# STM32F103C8T6.net
KiCad netlist of a schematic drawn in Altium Designer
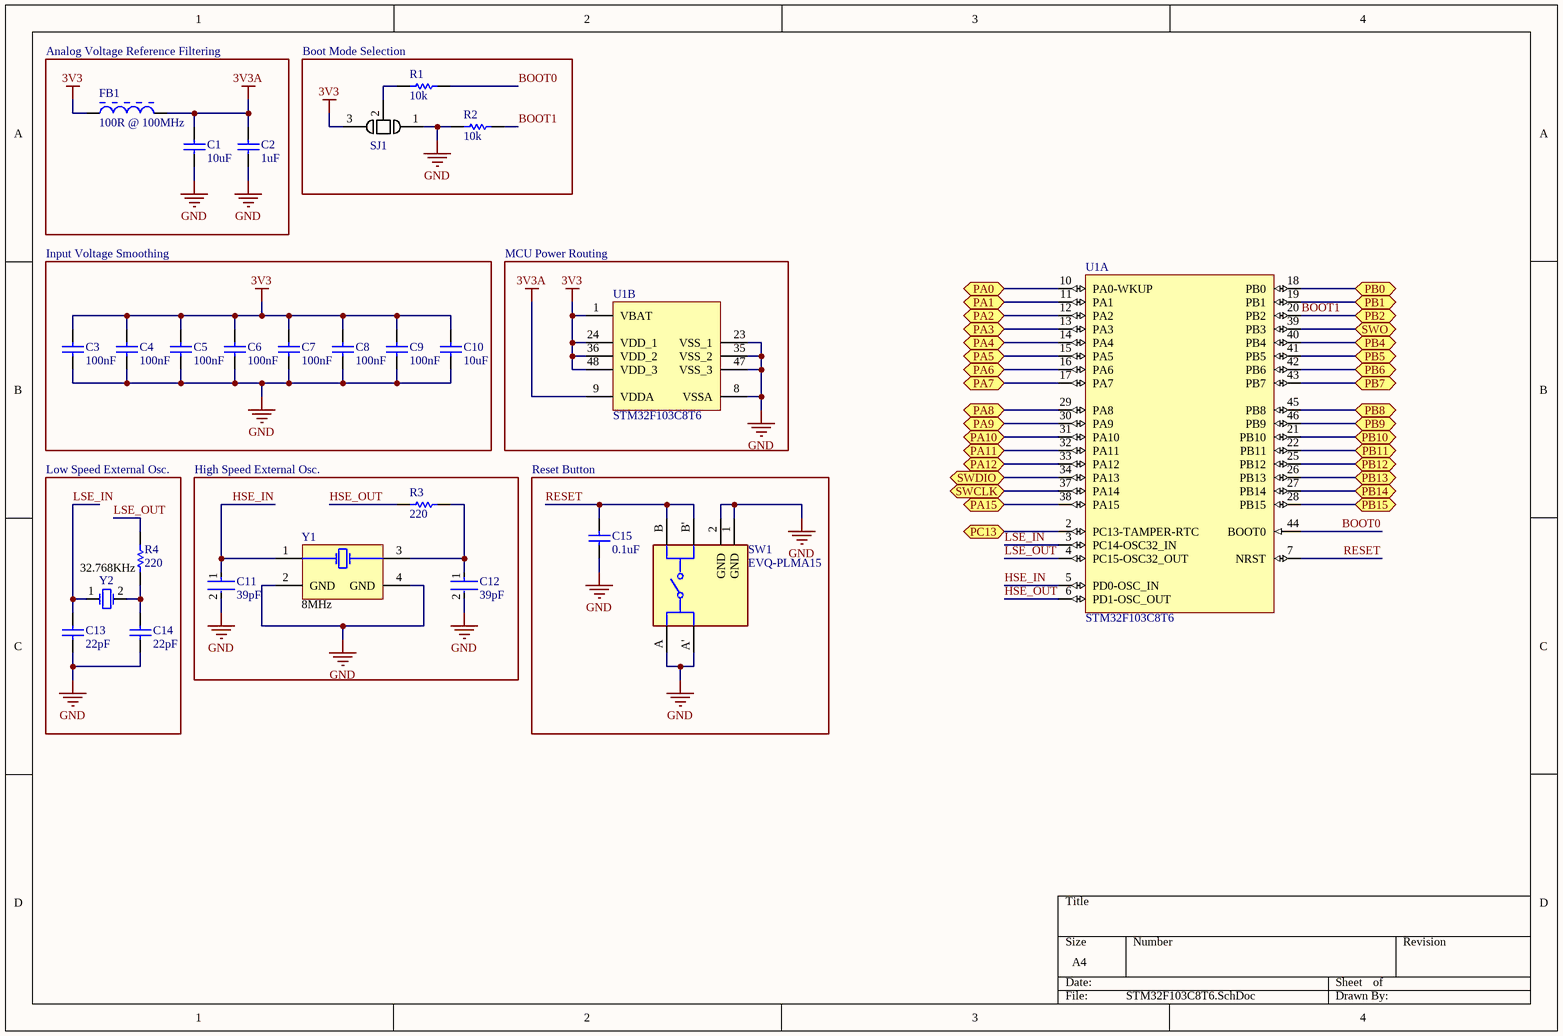
[diagram p0: STM32F103C8T6.SchDoc]

(export (version "E")
  (design (tool "Eeschema 10.0.6"))
  (components
    (comp (ref "C1")
      (value "10uF")
      (footprint "CAPC3216X180X50LL20T30")
      (description "Chip Capacitor, 10 uF, +/- 10%, 25 V, -55 to 85 degC, 1206 (3216 Metric), RoHS, Tape and Reel")
      (fields
        (field (name "MANUFACTURER") "Samsung Electro-Mechanics")
        (field (name "MANUFACTURER PART NUMBER") "CL31A106KAHNNNE")
      )
      (libsource (lib "Altium Content Vault") (part "CAP-NP-2"))
    )
    (comp (ref "C2")
      (value "1uF")
      (footprint "CAPC2013X140X50NL20T25")
      (fields
        (field (name "PART NUMBER") "C0805C105J4RACTU")
        (field (name "MANUFACTURER") "Kemet")
        (field (name "TOLERANCE") "5%")
      )
      (libsource (lib "Altium Content Vault") (part "CAP"))
    )
    (comp (ref "C3")
      (value "100nF")
      (footprint "CAPC2013X94X50LL20T25")
      (description "Chip Capacitor, 0.1 uF, +/- 5%, 50 V, -55 to 125 degC, 0805 (2012 Metric), RoHS, Tape and Reel")
      (fields (field (name "TOLERANCE") "5%") (field (name "MANUFACTURER") "AVX"))
      (libsource (lib "Altium Content Vault") (part "CAP-NP-2"))
    )
    (comp (ref "C4")
      (value "100nF")
      (footprint "CAPC2013X94X50LL20T25")
      (description "Chip Capacitor, 0.1 uF, +/- 5%, 50 V, -55 to 125 degC, 0805 (2012 Metric), RoHS, Tape and Reel")
      (fields (field (name "TOLERANCE") "5%") (field (name "MANUFACTURER") "AVX"))
      (libsource (lib "Altium Content Vault") (part "CAP-NP-2"))
    )
    (comp (ref "C5")
      (value "100nF")
      (footprint "CAPC2013X94X50LL20T25")
      (description "Chip Capacitor, 0.1 uF, +/- 5%, 50 V, -55 to 125 degC, 0805 (2012 Metric), RoHS, Tape and Reel")
      (fields (field (name "TOLERANCE") "5%") (field (name "MANUFACTURER") "AVX"))
      (libsource (lib "Altium Content Vault") (part "CAP-NP-2"))
    )
    (comp (ref "C6")
      (value "100nF")
      (footprint "CAPC2013X94X50LL20T25")
      (description "Chip Capacitor, 0.1 uF, +/- 5%, 50 V, -55 to 125 degC, 0805 (2012 Metric), RoHS, Tape and Reel")
      (fields (field (name "TOLERANCE") "5%") (field (name "MANUFACTURER") "AVX"))
      (libsource (lib "Altium Content Vault") (part "CAP-NP-2"))
    )
    (comp (ref "C7")
      (value "100nF")
      (footprint "CAPC2013X94X50LL20T25")
      (description "Chip Capacitor, 0.1 uF, +/- 5%, 50 V, -55 to 125 degC, 0805 (2012 Metric), RoHS, Tape and Reel")
      (fields (field (name "TOLERANCE") "5%") (field (name "MANUFACTURER") "AVX"))
      (libsource (lib "Altium Content Vault") (part "CAP-NP-2"))
    )
    (comp (ref "C8")
      (value "100nF")
      (footprint "CAPC2013X94X50LL20T25")
      (description "Chip Capacitor, 0.1 uF, +/- 5%, 50 V, -55 to 125 degC, 0805 (2012 Metric), RoHS, Tape and Reel")
      (fields (field (name "TOLERANCE") "5%") (field (name "MANUFACTURER") "AVX"))
      (libsource (lib "Altium Content Vault") (part "CAP-NP-2"))
    )
    (comp (ref "C9")
      (value "100nF")
      (footprint "CAPC2013X94X50LL20T25")
      (description "Chip Capacitor, 0.1 uF, +/- 5%, 50 V, -55 to 125 degC, 0805 (2012 Metric), RoHS, Tape and Reel")
      (fields (field (name "TOLERANCE") "5%") (field (name "MANUFACTURER") "AVX"))
      (libsource (lib "Altium Content Vault") (part "CAP-NP-2"))
    )
    (comp (ref "C10")
      (value "10uF")
      (footprint "CAPC3216X180X50LL20T30")
      (description "Chip Capacitor, 10 uF, +/- 10%, 25 V, -55 to 85 degC, 1206 (3216 Metric), RoHS, Tape and Reel")
      (fields
        (field (name "MANUFACTURER") "Samsung Electro-Mechanics")
        (field (name "MANUFACTURER PART NUMBER") "CL31A106KAHNNNE")
      )
      (libsource (lib "Altium Content Vault") (part "CAP-NP-2"))
    )
    (comp (ref "C11")
      (value "39pF")
      (footprint "FP-CL21-IPC_B")
      (description "CL21 Series 0805 39pF 50V ±5% Tolerance C0G Multilayer Ceramic Chip Capacitor")
      (fields (field (name "TOLERANCE") "5%") (field (name "VOLTAGE") "50V"))
      (libsource (lib "Altium Content Vault") (part "b4654b650e69147ec39a6b967a45e02"))
    )
    (comp (ref "C12")
      (value "39pF")
      (footprint "FP-CL21-IPC_B")
      (description "CL21 Series 0805 39pF 50V ±5% Tolerance C0G Multilayer Ceramic Chip Capacitor")
      (fields (field (name "TOLERANCE") "5%") (field (name "VOLTAGE") "50V"))
      (libsource (lib "Altium Content Vault") (part "b4654b650e69147ec39a6b967a45e02"))
    )
    (comp (ref "C13")
      (value "22pF")
      (footprint "CAPC2012X88X50ML20T25")
      (fields
        (field (name "MANUFACTURER") "Kemet")
        (field (name "PART NUMBER") "C0805C220J5GACTU")
        (field (name "TOLERANCE") "5%")
      )
      (libsource (lib "Altium Content Vault") (part "CAP"))
    )
    (comp (ref "C14")
      (value "22pF")
      (footprint "CAPC2012X88X50ML20T25")
      (fields
        (field (name "MANUFACTURER") "Kemet")
        (field (name "PART NUMBER") "C0805C220J5GACTU")
        (field (name "TOLERANCE") "5%")
      )
      (libsource (lib "Altium Content Vault") (part "CAP"))
    )
    (comp (ref "C15")
      (value "0.1uF")
      (footprint "CAPC2013X95X45ML10T25")
      (description "Chip Capacitor, 0.1 uF, +/- 10%, 50 V, 0805 (2012 Metric), RoHS, Tape and Reel")
      (fields
        (field (name "MANUFACTURER") "Samsung Electro-Mechanics")
        (field (name "MANUFACTURER PART NUMBER") "CL21B104KBCNNNC")
      )
      (libsource (lib "Altium Content Vault") (part "CAP-NP-2"))
    )
    (comp (ref "FB1")
      (value "100R @ 100MHz")
      (footprint "MURA-BLM18PG_KG-B25-CHIP-2_V1")
      (fields
        (field (name "PARTNUMBER") "BLM18PG121SN1D")
        (field (name "MANUFACTURER") "Murata")
        (field (name "TOLERANCE") "25%")
      )
      (libsource (lib "Altium Content Vault") (part "MURA-FB-2"))
    )
    (comp (ref "R1")
      (value "10k")
      (footprint "RESC2013X70X40LL20T20")
      (fields
        (field (name "PART NUMBER") "ERJ-6GEYJ103V")
        (field (name "MANUFACTURER") "Panasonic")
        (field (name "TOLERANCE") "5%")
      )
      (libsource (lib "Altium Content Vault") (part "RES"))
    )
    (comp (ref "R2")
      (value "10k")
      (footprint "RESC2013X70X40LL20T20")
      (fields
        (field (name "PART NUMBER") "ERJ-6GEYJ103V")
        (field (name "MANUFACTURER") "Panasonic")
        (field (name "TOLERANCE") "5%")
      )
      (libsource (lib "Altium Content Vault") (part "RES"))
    )
    (comp (ref "R3")
      (value "220")
      (footprint "RESC2013X70X40NL20T20")
      (fields
        (field (name "PART NUMBER") "ERJ6ENF2200V")
        (field (name "MANUFACTURER") "Panasonic")
        (field (name "MANUFACTURER PART NUMBER") "ERJ-6ENF2200V")
      )
      (libsource (lib "Altium Content Vault") (part "RES"))
    )
    (comp (ref "R4")
      (value "220")
      (footprint "RESC2013X70X40NL20T20")
      (fields
        (field (name "PART NUMBER") "ERJ6ENF2200V")
        (field (name "MANUFACTURER") "Panasonic")
        (field (name "MANUFACTURER PART NUMBER") "ERJ-6ENF2200V")
      )
      (libsource (lib "Altium Content Vault") (part "RES"))
    )
    (comp (ref "SJ1")
      (value "Switchable Jumper")
      (footprint "6mil Switchable")
      (description "Switchable Solder Jumper to choose between two connections.")
      (libsource (lib "Solder Jumpers") (part "Switchable Jumper"))
    )
    (comp (ref "SW1")
      (value "EVQ-PLMA15")
      (footprint "FP-EVQ-PLMA15-MFG")
      (description "SWITCH TACTILE SPST-NO 0.02A 15V")
      (fields
        (field (name "OCTOPART") "https://octopart.com/evq-plma15-panasonic-39850235")
        (field (name "MANUFACTURER") "Panasonic Electronic Components")
      )
      (libsource (lib "Altium Content Vault") (part "fc7b47d2e4813f0909612a6c4f63938"))
    )
    (comp (ref "U1")
      (value "STM32F103C8T6")
      (footprint "STM-LQFP48_L")
      (fields (field (name "MANUFACTURER") "STMicroelectronics"))
      (libsource (lib "Altium Content Vault") (part "MC-ARM-STM32F103X8_B-SQ48"))
    )
    (comp (ref "Y1")
      (value "8MHz")
      (footprint "ABRA-ABM3B_V")
      (description "Ceramic SMD Crystal, 8 MHz, +/- 20 ppm, 200 Ohm, -20 to 70 degC, 4-Pin SMD, RoHS, Tape and Reel")
      (fields
        (field (name "MANUFACTURER") "Abracon")
        (field (name "MANUFACTURER PART NUMBER") "ABM3B-8.000MHZ-B2-T")
      )
      (libsource (lib "Altium Content Vault") (part "XTAL-1-3-4"))
    )
    (comp (ref "Y2")
      (value "32.768KHz")
      (footprint "CMHT-CM315D-2_V")
      (description "Turning Fork Crystal Unit, 32.768 KHz, -40 to 85 degC, 2-Pin SMD, RoHS, Tape and Reel")
      (fields
        (field (name "MANUFACTURER") "Citizen Micro HumanTech")
        (field (name "MANUFACTURER PART NUMBER") "CM315D32768DZFT")
      )
      (libsource (lib "Altium Content Vault") (part "XTAL-1-2-2"))
    )
  )
  (nets
    (net (code "2") (name "/BOOT0") (class "Default")
      (node (ref "R1") (pin "2") (pinfunction "2_2") (pintype "passive"))
      (node (ref "U1") (pin "44") (pinfunction "BOOT0_44") (pintype "input"))
    )
    (net (code "3") (name "/BOOT1") (class "Default")
      (node (ref "R2") (pin "2") (pinfunction "2_2") (pintype "passive"))
      (node (ref "U1") (pin "20") (pinfunction "PB2_20") (pintype "bidirectional"))
    )
    (net (code "4") (name "/HSE_IN") (class "Default")
      (node (ref "C11") (pin "1") (pinfunction "1_1") (pintype "passive"))
      (node (ref "U1") (pin "5") (pinfunction "PD0-OSC_IN_5") (pintype "bidirectional"))
      (node (ref "Y1") (pin "1") (pinfunction "X1_1") (pintype "passive"))
    )
    (net (code "5") (name "/HSE_OUT") (class "Default")
      (node (ref "R3") (pin "2") (pinfunction "2_2") (pintype "passive"))
      (node (ref "U1") (pin "6") (pinfunction "PD1-OSC_OUT_6") (pintype "bidirectional"))
    )
    (net (code "6") (name "/LSE_IN") (class "Default")
      (node (ref "C13") (pin "2") (pinfunction "2_2") (pintype "passive"))
      (node (ref "U1") (pin "3") (pinfunction "PC14-OSC32_IN_3") (pintype "bidirectional"))
      (node (ref "Y2") (pin "1") (pinfunction "1_1") (pintype "passive"))
    )
    (net (code "7") (name "/LSE_OUT") (class "Default")
      (node (ref "R4") (pin "2") (pinfunction "2_2") (pintype "passive"))
      (node (ref "U1") (pin "4") (pinfunction "PC15-OSC32_OUT_4") (pintype "bidirectional"))
    )
    (net (code "8") (name "/PA0") (class "Default")
      (node (ref "U1") (pin "10") (pinfunction "PA0-WKUP_10") (pintype "bidirectional"))
    )
    (net (code "9") (name "/PA1") (class "Default")
      (node (ref "U1") (pin "11") (pinfunction "PA1_11") (pintype "bidirectional"))
    )
    (net (code "10") (name "/PA2") (class "Default")
      (node (ref "U1") (pin "12") (pinfunction "PA2_12") (pintype "bidirectional"))
    )
    (net (code "11") (name "/PA3") (class "Default")
      (node (ref "U1") (pin "13") (pinfunction "PA3_13") (pintype "bidirectional"))
    )
    (net (code "12") (name "/PA4") (class "Default")
      (node (ref "U1") (pin "14") (pinfunction "PA4_14") (pintype "bidirectional"))
    )
    (net (code "13") (name "/PA5") (class "Default")
      (node (ref "U1") (pin "15") (pinfunction "PA5_15") (pintype "bidirectional"))
    )
    (net (code "14") (name "/PA6") (class "Default")
      (node (ref "U1") (pin "16") (pinfunction "PA6_16") (pintype "bidirectional"))
    )
    (net (code "15") (name "/PA7") (class "Default")
      (node (ref "U1") (pin "17") (pinfunction "PA7_17") (pintype "bidirectional"))
    )
    (net (code "16") (name "/PA8") (class "Default")
      (node (ref "U1") (pin "29") (pinfunction "PA8_29") (pintype "bidirectional"))
    )
    (net (code "17") (name "/PA9") (class "Default")
      (node (ref "U1") (pin "30") (pinfunction "PA9_30") (pintype "bidirectional"))
    )
    (net (code "18") (name "/PA10") (class "Default")
      (node (ref "U1") (pin "31") (pinfunction "PA10_31") (pintype "bidirectional"))
    )
    (net (code "19") (name "/PA11") (class "Default")
      (node (ref "U1") (pin "32") (pinfunction "PA11_32") (pintype "bidirectional"))
    )
    (net (code "20") (name "/PA12") (class "Default")
      (node (ref "U1") (pin "33") (pinfunction "PA12_33") (pintype "bidirectional"))
    )
    (net (code "21") (name "/PA15") (class "Default")
      (node (ref "U1") (pin "38") (pinfunction "PA15_38") (pintype "bidirectional"))
    )
    (net (code "22") (name "/PB0") (class "Default")
      (node (ref "U1") (pin "18") (pinfunction "PB0_18") (pintype "bidirectional"))
    )
    (net (code "23") (name "/PB1") (class "Default")
      (node (ref "U1") (pin "19") (pinfunction "PB1_19") (pintype "bidirectional"))
    )
    (net (code "24") (name "/PB4") (class "Default")
      (node (ref "U1") (pin "40") (pinfunction "PB4_40") (pintype "bidirectional"))
    )
    (net (code "25") (name "/PB5") (class "Default")
      (node (ref "U1") (pin "41") (pinfunction "PB5_41") (pintype "bidirectional"))
    )
    (net (code "26") (name "/PB6") (class "Default")
      (node (ref "U1") (pin "42") (pinfunction "PB6_42") (pintype "bidirectional"))
    )
    (net (code "27") (name "/PB7") (class "Default")
      (node (ref "U1") (pin "43") (pinfunction "PB7_43") (pintype "bidirectional"))
    )
    (net (code "28") (name "/PB8") (class "Default")
      (node (ref "U1") (pin "45") (pinfunction "PB8_45") (pintype "bidirectional"))
    )
    (net (code "29") (name "/PB9") (class "Default")
      (node (ref "U1") (pin "46") (pinfunction "PB9_46") (pintype "bidirectional"))
    )
    (net (code "30") (name "/PB10") (class "Default")
      (node (ref "U1") (pin "21") (pinfunction "PB10_21") (pintype "bidirectional"))
    )
    (net (code "31") (name "/PB11") (class "Default")
      (node (ref "U1") (pin "22") (pinfunction "PB11_22") (pintype "bidirectional"))
    )
    (net (code "32") (name "/PB12") (class "Default")
      (node (ref "U1") (pin "25") (pinfunction "PB12_25") (pintype "bidirectional"))
    )
    (net (code "33") (name "/PB13") (class "Default")
      (node (ref "U1") (pin "26") (pinfunction "PB13_26") (pintype "bidirectional"))
    )
    (net (code "34") (name "/PB14") (class "Default")
      (node (ref "U1") (pin "27") (pinfunction "PB14_27") (pintype "bidirectional"))
    )
    (net (code "35") (name "/PB15") (class "Default")
      (node (ref "U1") (pin "28") (pinfunction "PB15_28") (pintype "bidirectional"))
    )
    (net (code "36") (name "/PC13") (class "Default")
      (node (ref "U1") (pin "2") (pinfunction "PC13-TAMPER-RTC_2") (pintype "bidirectional"))
    )
    (net (code "37") (name "/RESET") (class "Default")
      (node (ref "C15") (pin "1") (pinfunction "1_1") (pintype "passive"))
      (node (ref "SW1") (pin "B") (pinfunction "B_B") (pintype "passive"))
      (node (ref "SW1") (pin "B'") (pinfunction "B'_B'") (pintype "passive"))
      (node (ref "U1") (pin "7") (pinfunction "NRST_7") (pintype "bidirectional"))
    )
    (net (code "38") (name "/SWCLK") (class "Default")
      (node (ref "U1") (pin "37") (pinfunction "PA14_37") (pintype "bidirectional"))
    )
    (net (code "39") (name "/SWDIO") (class "Default")
      (node (ref "U1") (pin "34") (pinfunction "PA13_34") (pintype "bidirectional"))
    )
    (net (code "40") (name "/SWO") (class "Default")
      (node (ref "U1") (pin "39") (pinfunction "PB3_39") (pintype "bidirectional"))
    )
    (net (code "41") (name "3V3") (class "Default")
      (node (ref "C10") (pin "2") (pinfunction "2_2") (pintype "passive"))
      (node (ref "C3") (pin "2") (pinfunction "2_2") (pintype "passive"))
      (node (ref "C4") (pin "2") (pinfunction "2_2") (pintype "passive"))
      (node (ref "C5") (pin "2") (pinfunction "2_2") (pintype "passive"))
      (node (ref "C6") (pin "2") (pinfunction "2_2") (pintype "passive"))
      (node (ref "C7") (pin "2") (pinfunction "2_2") (pintype "passive"))
      (node (ref "C8") (pin "2") (pinfunction "2_2") (pintype "passive"))
      (node (ref "C9") (pin "2") (pinfunction "2_2") (pintype "passive"))
      (node (ref "FB1") (pin "1") (pinfunction "1_1") (pintype "passive"))
      (node (ref "SJ1") (pin "3") (pintype "passive"))
      (node (ref "U1") (pin "1") (pinfunction "VBAT_1") (pintype "power_in"))
      (node (ref "U1") (pin "24") (pinfunction "VDD_1_24") (pintype "power_in"))
      (node (ref "U1") (pin "36") (pinfunction "VDD_2_36") (pintype "power_in"))
      (node (ref "U1") (pin "48") (pinfunction "VDD_3_48") (pintype "power_in"))
    )
    (net (code "42") (name "3V3A") (class "Default")
      (node (ref "C1") (pin "2") (pinfunction "2_2") (pintype "passive"))
      (node (ref "C2") (pin "2") (pinfunction "2_2") (pintype "passive"))
      (node (ref "FB1") (pin "2") (pinfunction "2_2") (pintype "passive"))
      (node (ref "U1") (pin "9") (pinfunction "VDDA_9") (pintype "power_in"))
    )
    (net (code "43") (name "GND") (class "Default")
      (node (ref "C1") (pin "1") (pinfunction "1_1") (pintype "passive"))
      (node (ref "C10") (pin "1") (pinfunction "1_1") (pintype "passive"))
      (node (ref "C11") (pin "2") (pinfunction "2_2") (pintype "passive"))
      (node (ref "C12") (pin "2") (pinfunction "2_2") (pintype "passive"))
      (node (ref "C13") (pin "1") (pinfunction "1_1") (pintype "passive"))
      (node (ref "C14") (pin "1") (pinfunction "1_1") (pintype "passive"))
      (node (ref "C15") (pin "2") (pinfunction "2_2") (pintype "passive"))
      (node (ref "C2") (pin "1") (pinfunction "1_1") (pintype "passive"))
      (node (ref "C3") (pin "1") (pinfunction "1_1") (pintype "passive"))
      (node (ref "C4") (pin "1") (pinfunction "1_1") (pintype "passive"))
      (node (ref "C5") (pin "1") (pinfunction "1_1") (pintype "passive"))
      (node (ref "C6") (pin "1") (pinfunction "1_1") (pintype "passive"))
      (node (ref "C7") (pin "1") (pinfunction "1_1") (pintype "passive"))
      (node (ref "C8") (pin "1") (pinfunction "1_1") (pintype "passive"))
      (node (ref "C9") (pin "1") (pinfunction "1_1") (pintype "passive"))
      (node (ref "R2") (pin "1") (pinfunction "1_1") (pintype "passive"))
      (node (ref "SJ1") (pin "1") (pintype "passive"))
      (node (ref "SW1") (pin "1") (pinfunction "GND_1") (pintype "power_in"))
      (node (ref "SW1") (pin "2") (pinfunction "GND_2") (pintype "power_in"))
      (node (ref "SW1") (pin "A") (pinfunction "A_A") (pintype "passive"))
      (node (ref "SW1") (pin "A'") (pinfunction "A'_A'") (pintype "passive"))
      (node (ref "U1") (pin "23") (pinfunction "VSS_1_23") (pintype "power_in"))
      (node (ref "U1") (pin "35") (pinfunction "VSS_2_35") (pintype "power_in"))
      (node (ref "U1") (pin "47") (pinfunction "VSS_3_47") (pintype "power_in"))
      (node (ref "U1") (pin "8") (pinfunction "VSSA_8") (pintype "power_in"))
      (node (ref "Y1") (pin "2") (pinfunction "GND_2") (pintype "power_in"))
      (node (ref "Y1") (pin "4") (pinfunction "GND_4") (pintype "power_in"))
    )
    (net (code "44") (name "Net-(C14-Pad2)") (class "Default")
      (node (ref "C14") (pin "2") (pinfunction "2_2") (pintype "passive"))
      (node (ref "R4") (pin "1") (pinfunction "1_1") (pintype "passive"))
      (node (ref "Y2") (pin "2") (pinfunction "2_2") (pintype "passive"))
    )
    (net (code "45") (name "Net-(R1-Pad1)") (class "Default")
      (node (ref "R1") (pin "1") (pinfunction "1_1") (pintype "passive"))
      (node (ref "SJ1") (pin "2") (pintype "passive"))
    )
    (net (code "46") (name "Net-(Y1-X2)") (class "Default")
      (node (ref "C12") (pin "1") (pinfunction "1_1") (pintype "passive"))
      (node (ref "R3") (pin "1") (pinfunction "1_1") (pintype "passive"))
      (node (ref "Y1") (pin "3") (pinfunction "X2_3") (pintype "passive"))
    )
  )
)
